# 2_-_Position2Go_Microcontroller.net
KiCad netlist of a schematic drawn in Altium Designer
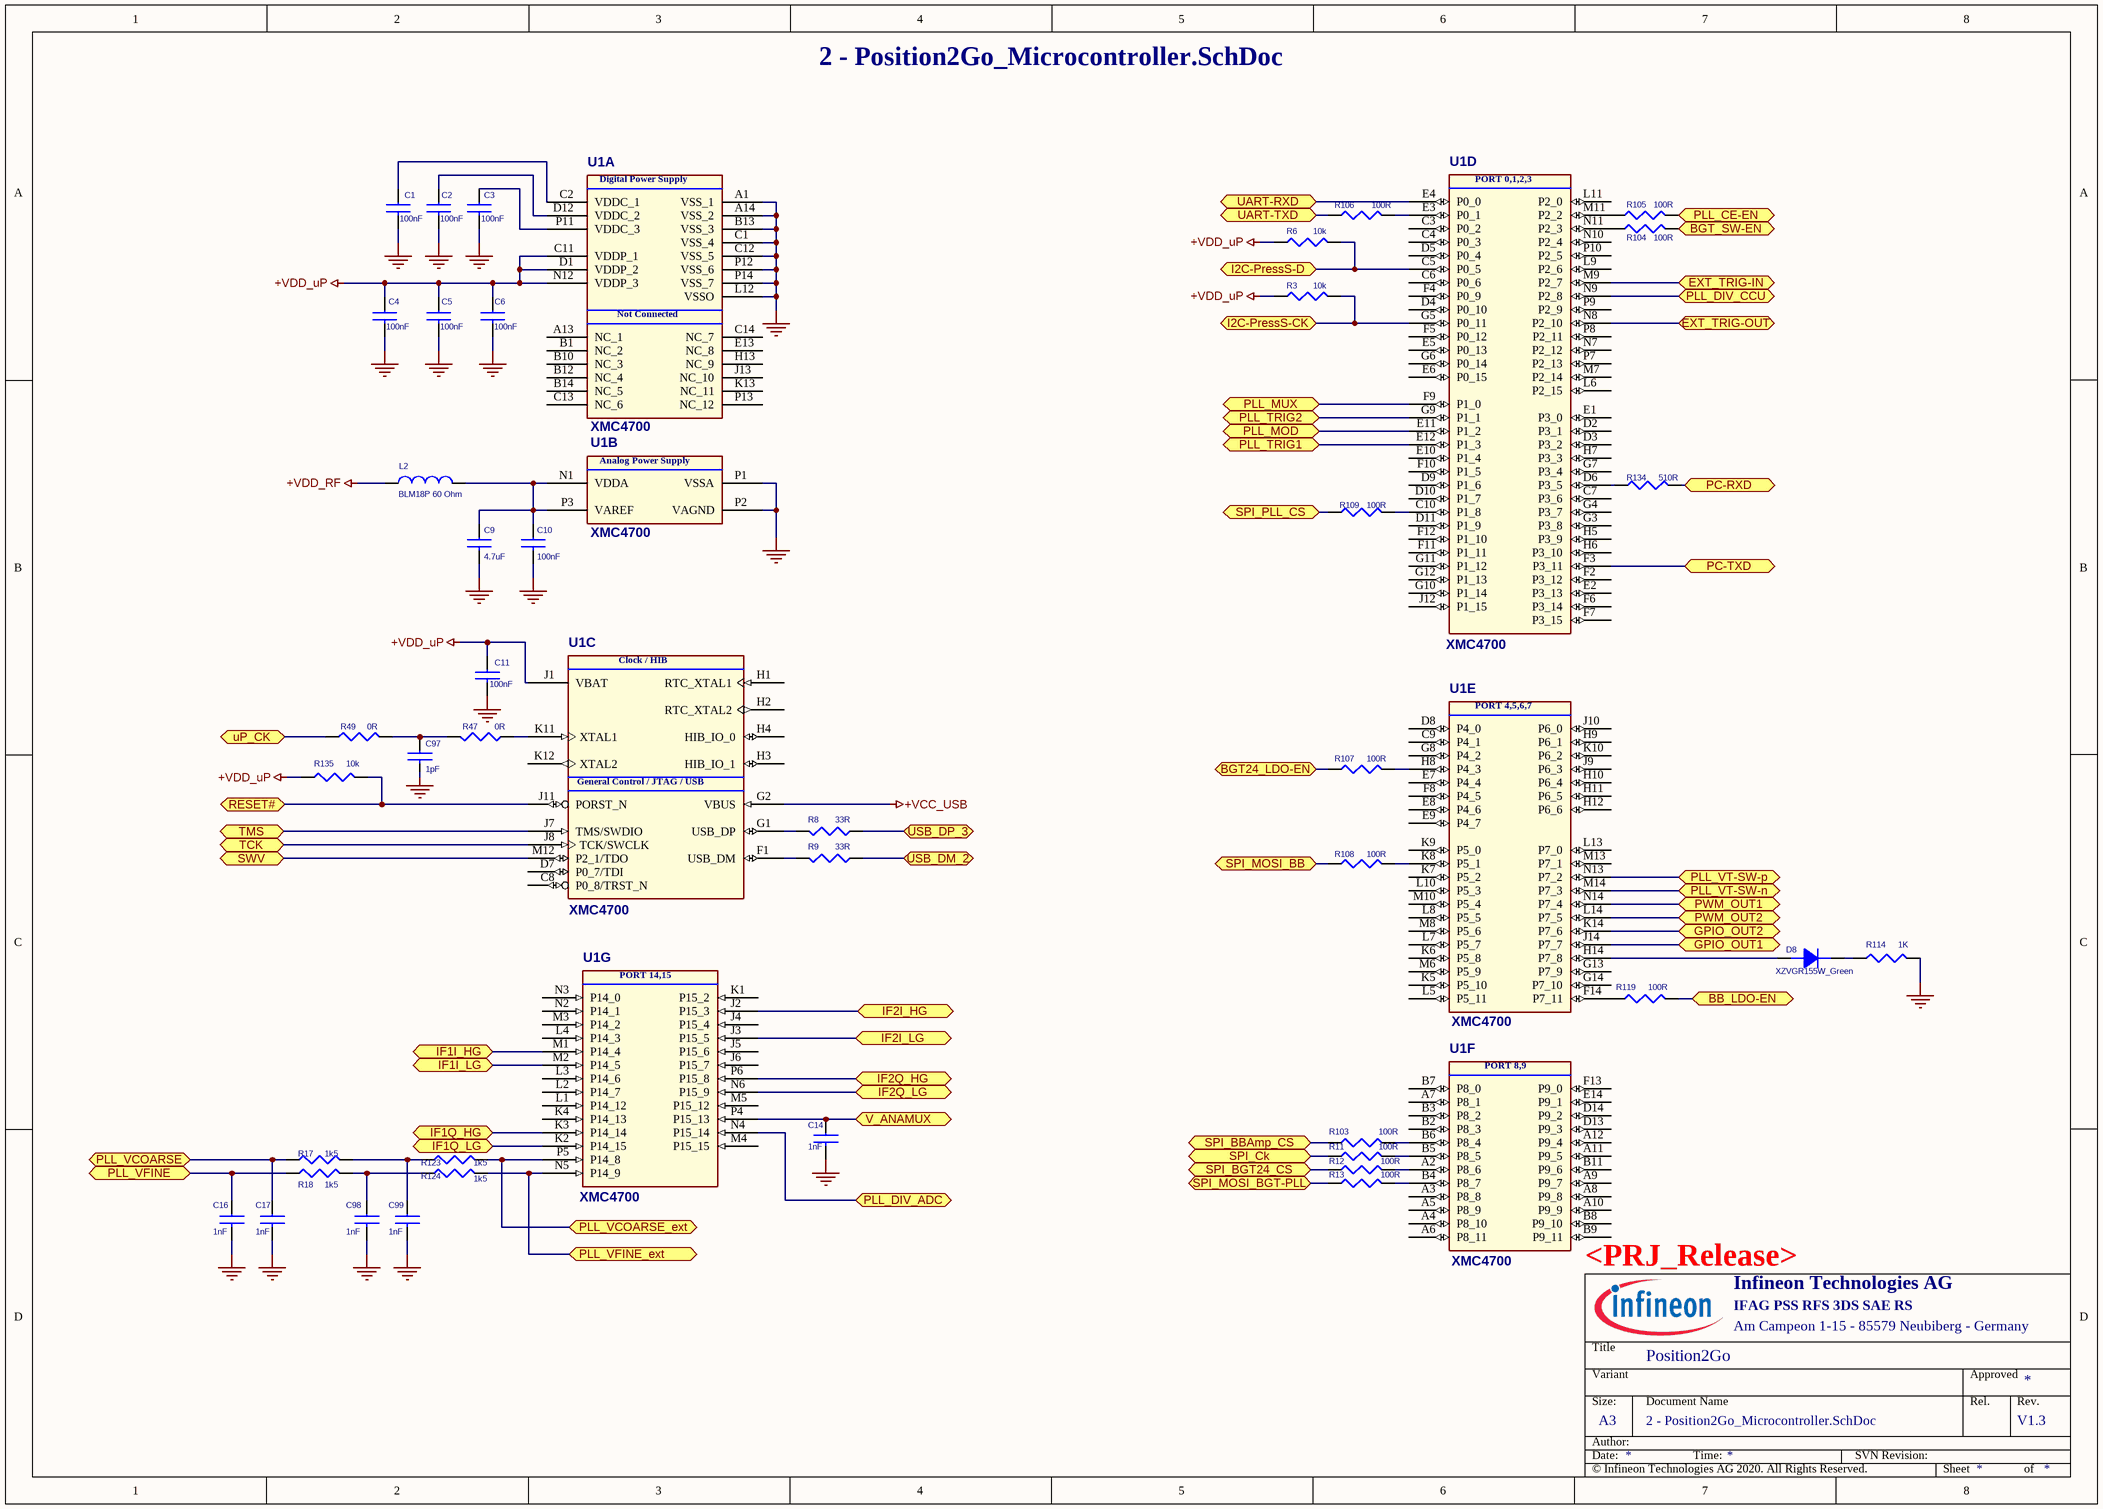
[diagram p0: 2 - Position2Go_Microcontroller.SchDoc]

(export (version "E")
  (design (tool "Eeschema 10.0.6"))
  (components
    (comp (ref "C1")
      (value "100nF")
      (footprint "C_0201")
      (description "100nF  ±10%  35V  X5R")
      (fields (field (name "VOLTAGE") "35V") (field (name "TOLERANCE") "10%"))
      (libsource (lib "*") (part "100nF_Dup1"))
    )
    (comp (ref "C2")
      (value "100nF")
      (footprint "C_0201")
      (description "100nF  ±10%  35V  X5R")
      (fields (field (name "VOLTAGE") "35V") (field (name "TOLERANCE") "10%"))
      (libsource (lib "*") (part "100nF_Dup1"))
    )
    (comp (ref "C3")
      (value "100nF")
      (footprint "C_0201")
      (description "100nF  ±10%  35V  X5R")
      (fields (field (name "VOLTAGE") "35V") (field (name "TOLERANCE") "10%"))
      (libsource (lib "*") (part "100nF_Dup1"))
    )
    (comp (ref "C4")
      (value "100nF")
      (footprint "C_0201")
      (description "100nF  ±10%  35V  X5R")
      (fields (field (name "VOLTAGE") "35V") (field (name "TOLERANCE") "10%"))
      (libsource (lib "*") (part "100nF_Dup1"))
    )
    (comp (ref "C5")
      (value "100nF")
      (footprint "C_0201")
      (description "100nF  ±10%  35V  X5R")
      (fields (field (name "VOLTAGE") "35V") (field (name "TOLERANCE") "10%"))
      (libsource (lib "*") (part "100nF_Dup1"))
    )
    (comp (ref "C6")
      (value "100nF")
      (footprint "C_0201")
      (description "100nF  ±10%  35V  X5R")
      (fields (field (name "VOLTAGE") "35V") (field (name "TOLERANCE") "10%"))
      (libsource (lib "*") (part "100nF_Dup1"))
    )
    (comp (ref "C9")
      (value "4.7uF")
      (footprint "0402_durac")
      (fields (field (name "VOLTAGE") "10V") (field (name "TOLERANCE") "10%"))
      (libsource (lib "*") (part "4.7UF"))
    )
    (comp (ref "C10")
      (value "100nF")
      (footprint "C_0201")
      (description "100nF  ±10%  35V  X5R")
      (fields (field (name "VOLTAGE") "35V") (field (name "TOLERANCE") "10%"))
      (libsource (lib "*") (part "100nF_Dup1"))
    )
    (comp (ref "C11")
      (value "100nF")
      (footprint "C_0201")
      (description "100nF  ±10%  35V  X5R")
      (fields (field (name "VOLTAGE") "35V") (field (name "TOLERANCE") "10%"))
      (libsource (lib "*") (part "100nF_Dup1"))
    )
    (comp (ref "C14")
      (value "1nF")
      (footprint "C_0201")
      (fields (field (name "TOLERANCE") "10%") (field (name "VOLTAGE") "25V"))
      (libsource (lib "*") (part "1nF"))
    )
    (comp (ref "C16")
      (value "1nF")
      (footprint "C_0201")
      (fields (field (name "TOLERANCE") "10%") (field (name "VOLTAGE") "25V"))
      (libsource (lib "*") (part "1nF"))
    )
    (comp (ref "C17")
      (value "1nF")
      (footprint "C_0201")
      (fields (field (name "TOLERANCE") "10%") (field (name "VOLTAGE") "25V"))
      (libsource (lib "*") (part "1nF"))
    )
    (comp (ref "C97")
      (value "1pF")
      (footprint "C_0201")
      (fields (field (name "TOLERANCE") "±0,1 pF") (field (name "VOLTAGE") "25V"))
      (libsource (lib "*") (part "1pF"))
    )
    (comp (ref "C98")
      (value "1nF")
      (footprint "0402_durac")
      (fields (field (name "VOLTAGE") "50V") (field (name "TOLERANCE") "5%"))
      (libsource (lib "*") (part "1.0nF"))
    )
    (comp (ref "C99")
      (value "1nF")
      (footprint "0402_durac")
      (fields (field (name "VOLTAGE") "50V") (field (name "TOLERANCE") "5%"))
      (libsource (lib "*") (part "1.0nF"))
    )
    (comp (ref "D8")
      (value "XZVGR155W_Green")
      (footprint "LED_0201")
      (libsource (lib "*") (part "LED_0201_GREEN"))
    )
    (comp (ref "L2")
      (value "BLM18P 60 Ohm")
      (footprint "L_0603")
      (libsource (lib "*") (part "blm18 p 60 ohm"))
    )
    (comp (ref "R3")
      (value "10k")
      (footprint "R_0201")
      (fields (field (name "TOLERANCE") "1%") (field (name "POWER") "0.063W"))
      (libsource (lib "*") (part "10K_Dup1"))
    )
    (comp (ref "R6")
      (value "10k")
      (footprint "R_0201")
      (fields (field (name "TOLERANCE") "1%") (field (name "POWER") "0.063W"))
      (libsource (lib "*") (part "10K_Dup1"))
    )
    (comp (ref "R8") (value "33R") (footprint "0402_durac") (libsource (lib "*") (part "RESISTOR")))
    (comp (ref "R9") (value "33R") (footprint "0402_durac") (libsource (lib "*") (part "RESISTOR")))
    (comp (ref "R11")
      (value "100R")
      (footprint "R_0201")
      (fields (field (name "TOLERANCE") "1%") (field (name "POWER") "0.063W"))
      (libsource (lib "*") (part "100"))
    )
    (comp (ref "R12")
      (value "100R")
      (footprint "R_0201")
      (fields (field (name "TOLERANCE") "1%") (field (name "POWER") "0.063W"))
      (libsource (lib "*") (part "100"))
    )
    (comp (ref "R13")
      (value "100R")
      (footprint "R_0201")
      (fields (field (name "TOLERANCE") "1%") (field (name "POWER") "0.063W"))
      (libsource (lib "*") (part "100"))
    )
    (comp (ref "R17")
      (value "1k5")
      (footprint "R_0201")
      (fields (field (name "TOLERANCE") "1%") (field (name "POWER") "0.063W"))
      (libsource (lib "*") (part "1k5"))
    )
    (comp (ref "R18")
      (value "1k5")
      (footprint "R_0201")
      (fields (field (name "TOLERANCE") "1%") (field (name "POWER") "0.063W"))
      (libsource (lib "*") (part "1k5"))
    )
    (comp (ref "R47")
      (value "0R")
      (footprint "R_0201")
      (fields (field (name "TOLERANCE") "1%") (field (name "POWER") "0.063W"))
      (libsource (lib "*") (part "0_Dup2"))
    )
    (comp (ref "R49")
      (value "0R")
      (footprint "R_0201")
      (fields (field (name "TOLERANCE") "1%") (field (name "POWER") "0.063W"))
      (libsource (lib "*") (part "0_Dup2"))
    )
    (comp (ref "R103")
      (value "100R")
      (footprint "R_0201")
      (fields (field (name "TOLERANCE") "1%") (field (name "POWER") "0.063W"))
      (libsource (lib "*") (part "100"))
    )
    (comp (ref "R104")
      (value "100R")
      (footprint "R_0201")
      (fields (field (name "TOLERANCE") "1%") (field (name "POWER") "0.063W"))
      (libsource (lib "*") (part "100"))
    )
    (comp (ref "R105")
      (value "100R")
      (footprint "R_0201")
      (fields (field (name "TOLERANCE") "1%") (field (name "POWER") "0.063W"))
      (libsource (lib "*") (part "100"))
    )
    (comp (ref "R106")
      (value "100R")
      (footprint "R_0201")
      (fields (field (name "TOLERANCE") "1%") (field (name "POWER") "0.063W"))
      (libsource (lib "*") (part "100"))
    )
    (comp (ref "R107")
      (value "100R")
      (footprint "R_0201")
      (fields (field (name "TOLERANCE") "1%") (field (name "POWER") "0.063W"))
      (libsource (lib "*") (part "100"))
    )
    (comp (ref "R108")
      (value "100R")
      (footprint "R_0201")
      (fields (field (name "TOLERANCE") "1%") (field (name "POWER") "0.063W"))
      (libsource (lib "*") (part "100"))
    )
    (comp (ref "R109")
      (value "100R")
      (footprint "R_0201")
      (fields (field (name "TOLERANCE") "1%") (field (name "POWER") "0.063W"))
      (libsource (lib "*") (part "100"))
    )
    (comp (ref "R114")
      (value "1K")
      (footprint "R_0201")
      (fields (field (name "POWER") "0.063W") (field (name "TOLERANCE") "1%"))
      (libsource (lib "*") (part "1K"))
    )
    (comp (ref "R119")
      (value "100R")
      (footprint "R_0201")
      (fields (field (name "TOLERANCE") "1%") (field (name "POWER") "0.063W"))
      (libsource (lib "*") (part "100"))
    )
    (comp (ref "R123")
      (value "1k5")
      (footprint "R_0201")
      (fields (field (name "TOLERANCE") "1%") (field (name "POWER") "0.063W"))
      (libsource (lib "*") (part "1k5"))
    )
    (comp (ref "R124")
      (value "1k5")
      (footprint "R_0201")
      (fields (field (name "TOLERANCE") "1%") (field (name "POWER") "0.063W"))
      (libsource (lib "*") (part "1k5"))
    )
    (comp (ref "R134")
      (value "510R")
      (footprint "0402_durac")
      (fields (field (name "POWER") "0.063W") (field (name "TOLERANCE") "1%"))
      (libsource (lib "*") (part "510"))
    )
    (comp (ref "R135")
      (value "10k")
      (footprint "R_0201")
      (fields (field (name "TOLERANCE") "1%") (field (name "POWER") "0.063W"))
      (libsource (lib "*") (part "10K_Dup1"))
    )
    (comp (ref "U1")
      (value "XMC4700")
      (footprint "BGA196C80P14X14_1200X1200X170")
      (libsource (lib "*") (part "XMC4700-E196F2048"))
    )
  )
  (nets
    (net (code "1") (name "+VCC_USB") (class "Default")
      (node (ref "U1") (pin "G2") (pinfunction "VBUS_G2") (pintype "input"))
    )
    (net (code "2") (name "+VDD_RF") (class "Default")
      (node (ref "L2") (pin "1") (pinfunction "1_1") (pintype "passive"))
    )
    (net (code "3") (name "+VDD_uP") (class "Default")
      (node (ref "C11") (pin "1") (pinfunction "1_1") (pintype "passive"))
      (node (ref "C4") (pin "1") (pinfunction "1_1") (pintype "passive"))
      (node (ref "C5") (pin "1") (pinfunction "1_1") (pintype "passive"))
      (node (ref "C6") (pin "1") (pinfunction "1_1") (pintype "passive"))
      (node (ref "R135") (pin "2") (pinfunction "2_2") (pintype "passive"))
      (node (ref "R3") (pin "1") (pinfunction "1_1") (pintype "passive"))
      (node (ref "R6") (pin "2") (pinfunction "2_2") (pintype "passive"))
      (node (ref "U1") (pin "C11") (pinfunction "VDDP_1_C11") (pintype "power_in"))
      (node (ref "U1") (pin "D1") (pinfunction "VDDP_2_D1") (pintype "power_in"))
      (node (ref "U1") (pin "J1") (pinfunction "VBAT_J1") (pintype "power_in"))
      (node (ref "U1") (pin "N12") (pinfunction "VDDP_3_N12") (pintype "power_in"))
    )
    (net (code "4") (name "/BB_LDO-EN") (class "Default")
      (node (ref "R119") (pin "1") (pinfunction "1_1") (pintype "passive"))
    )
    (net (code "5") (name "/BGT24_LDO-EN") (class "Default")
      (node (ref "R107") (pin "1") (pinfunction "1_1") (pintype "passive"))
    )
    (net (code "6") (name "/BGT_SW-EN") (class "Default")
      (node (ref "R104") (pin "2") (pinfunction "2_2") (pintype "passive"))
    )
    (net (code "7") (name "/EXT_TRIG-IN") (class "Default")
      (node (ref "U1") (pin "M9") (pinfunction "P2_7_M9") (pintype "bidirectional"))
    )
    (net (code "8") (name "/EXT_TRIG-OUT") (class "Default")
      (node (ref "U1") (pin "N8") (pinfunction "P2_10_N8") (pintype "bidirectional"))
    )
    (net (code "9") (name "/GPIO_OUT1") (class "Default")
      (node (ref "U1") (pin "J14") (pinfunction "P7_7_J14") (pintype "bidirectional"))
    )
    (net (code "10") (name "/GPIO_OUT2") (class "Default")
      (node (ref "U1") (pin "K14") (pinfunction "P7_6_K14") (pintype "bidirectional"))
    )
    (net (code "11") (name "/I2C-PressS-CK") (class "Default")
      (node (ref "R3") (pin "2") (pinfunction "2_2") (pintype "passive"))
      (node (ref "U1") (pin "G5") (pinfunction "P0_11_G5") (pintype "bidirectional"))
    )
    (net (code "12") (name "/I2C-PressS-D") (class "Default")
      (node (ref "R6") (pin "1") (pinfunction "1_1") (pintype "passive"))
      (node (ref "U1") (pin "C5") (pinfunction "P0_5_C5") (pintype "bidirectional"))
    )
    (net (code "13") (name "/IF1I_HG") (class "Default")
      (node (ref "U1") (pin "M1") (pinfunction "P14_4_M1") (pintype "input"))
    )
    (net (code "14") (name "/IF1I_LG") (class "Default")
      (node (ref "U1") (pin "M2") (pinfunction "P14_5_M2") (pintype "input"))
    )
    (net (code "15") (name "/IF1Q_HG") (class "Default")
      (node (ref "U1") (pin "K3") (pinfunction "P14_14_K3") (pintype "input"))
    )
    (net (code "16") (name "/IF1Q_LG") (class "Default")
      (node (ref "U1") (pin "K2") (pinfunction "P14_15_K2") (pintype "input"))
    )
    (net (code "17") (name "/IF2I_HG") (class "Default")
      (node (ref "U1") (pin "J2") (pinfunction "P15_3_J2") (pintype "input"))
    )
    (net (code "18") (name "/IF2I_LG") (class "Default")
      (node (ref "U1") (pin "J3") (pinfunction "P15_5_J3") (pintype "input"))
    )
    (net (code "19") (name "/IF2Q_HG") (class "Default")
      (node (ref "U1") (pin "P6") (pinfunction "P15_8_P6") (pintype "input"))
    )
    (net (code "20") (name "/IF2Q_LG") (class "Default")
      (node (ref "U1") (pin "N6") (pinfunction "P15_9_N6") (pintype "input"))
    )
    (net (code "21") (name "/PC-RXD") (class "Default")
      (node (ref "R134") (pin "2") (pinfunction "2_2") (pintype "passive"))
    )
    (net (code "22") (name "/PC-TXD") (class "Default")
      (node (ref "U1") (pin "F3") (pinfunction "P3_11_F3") (pintype "bidirectional"))
    )
    (net (code "23") (name "/PLL_CE-EN") (class "Default")
      (node (ref "R105") (pin "2") (pinfunction "2_2") (pintype "passive"))
    )
    (net (code "24") (name "/PLL_DIV_ADC") (class "Default")
      (node (ref "U1") (pin "N4") (pinfunction "P15_14_N4") (pintype "input"))
    )
    (net (code "25") (name "/PLL_DIV_CCU") (class "Default")
      (node (ref "U1") (pin "N9") (pinfunction "P2_8_N9") (pintype "bidirectional"))
    )
    (net (code "26") (name "/PLL_MOD") (class "Default")
      (node (ref "U1") (pin "E11") (pinfunction "P1_2_E11") (pintype "bidirectional"))
    )
    (net (code "27") (name "/PLL_MUX") (class "Default")
      (node (ref "U1") (pin "F9") (pinfunction "P1_0_F9") (pintype "bidirectional"))
    )
    (net (code "28") (name "/PLL_TRIG1") (class "Default")
      (node (ref "U1") (pin "E12") (pinfunction "P1_3_E12") (pintype "bidirectional"))
    )
    (net (code "29") (name "/PLL_TRIG2") (class "Default")
      (node (ref "U1") (pin "G9") (pinfunction "P1_1_G9") (pintype "bidirectional"))
    )
    (net (code "30") (name "/PLL_VCOARSE") (class "Default")
      (node (ref "C17") (pin "1") (pinfunction "1_1") (pintype "passive"))
      (node (ref "R17") (pin "1") (pinfunction "1_1") (pintype "passive"))
    )
    (net (code "31") (name "/PLL_VCOARSE_ext") (class "Default")
      (node (ref "R123") (pin "2") (pinfunction "2_2") (pintype "passive"))
      (node (ref "U1") (pin "P5") (pinfunction "P14_8_P5") (pintype "input"))
    )
    (net (code "32") (name "/PLL_VFINE") (class "Default")
      (node (ref "C16") (pin "1") (pinfunction "1_1") (pintype "passive"))
      (node (ref "R18") (pin "1") (pinfunction "1_1") (pintype "passive"))
    )
    (net (code "33") (name "/PLL_VFINE_ext") (class "Default")
      (node (ref "R124") (pin "2") (pinfunction "2_2") (pintype "passive"))
      (node (ref "U1") (pin "N5") (pinfunction "P14_9_N5") (pintype "input"))
    )
    (net (code "34") (name "/PLL_VT-SW-n") (class "Default")
      (node (ref "U1") (pin "M14") (pinfunction "P7_3_M14") (pintype "bidirectional"))
    )
    (net (code "35") (name "/PLL_VT-SW-p") (class "Default")
      (node (ref "U1") (pin "N13") (pinfunction "P7_2_N13") (pintype "bidirectional"))
    )
    (net (code "36") (name "/PWM_OUT1") (class "Default")
      (node (ref "U1") (pin "N14") (pinfunction "P7_4_N14") (pintype "bidirectional"))
    )
    (net (code "37") (name "/PWM_OUT2") (class "Default")
      (node (ref "U1") (pin "L14") (pinfunction "P7_5_L14") (pintype "bidirectional"))
    )
    (net (code "38") (name "/RESET#") (class "Default")
      (node (ref "R135") (pin "1") (pinfunction "1_1") (pintype "passive"))
      (node (ref "U1") (pin "J11") (pinfunction "PORST_N_J11") (pintype "bidirectional"))
    )
    (net (code "39") (name "/SPI_BBAmp_CS") (class "Default")
      (node (ref "R103") (pin "1") (pinfunction "1_1") (pintype "passive"))
    )
    (net (code "40") (name "/SPI_BGT24_CS") (class "Default")
      (node (ref "R12") (pin "1") (pinfunction "1_1") (pintype "passive"))
    )
    (net (code "41") (name "/SPI_Ck") (class "Default")
      (node (ref "R11") (pin "1") (pinfunction "1_1") (pintype "passive"))
    )
    (net (code "42") (name "/SPI_MOSI_BB") (class "Default")
      (node (ref "R108") (pin "1") (pinfunction "1_1") (pintype "passive"))
    )
    (net (code "43") (name "/SPI_MOSI_BGT-PLL") (class "Default")
      (node (ref "R13") (pin "1") (pinfunction "1_1") (pintype "passive"))
    )
    (net (code "44") (name "/SPI_PLL_CS") (class "Default")
      (node (ref "R109") (pin "2") (pinfunction "2_2") (pintype "passive"))
    )
    (net (code "45") (name "/SWV") (class "Default")
      (node (ref "U1") (pin "M12") (pinfunction "P2_1/TDO_M12") (pintype "bidirectional"))
    )
    (net (code "46") (name "/TCK") (class "Default")
      (node (ref "U1") (pin "J8") (pinfunction "TCK/SWCLK_J8") (pintype "input"))
    )
    (net (code "47") (name "/TMS") (class "Default")
      (node (ref "U1") (pin "J7") (pinfunction "TMS/SWDIO_J7") (pintype "input"))
    )
    (net (code "48") (name "/UART-RXD") (class "Default")
      (node (ref "U1") (pin "E4") (pinfunction "P0_0_E4") (pintype "bidirectional"))
    )
    (net (code "49") (name "/UART-TXD") (class "Default")
      (node (ref "R106") (pin "1") (pinfunction "1_1") (pintype "passive"))
    )
    (net (code "50") (name "/USB_DM_2") (class "Default")
      (node (ref "R9") (pin "1") (pinfunction "1_1") (pintype "passive"))
    )
    (net (code "51") (name "/USB_DP_3") (class "Default")
      (node (ref "R8") (pin "1") (pinfunction "1_1") (pintype "passive"))
    )
    (net (code "52") (name "/V_ANAMUX") (class "Default")
      (node (ref "C14") (pin "1") (pinfunction "1_1") (pintype "passive"))
      (node (ref "U1") (pin "P4") (pinfunction "P15_13_P4") (pintype "input"))
    )
    (net (code "53") (name "/uP_CK") (class "Default")
      (node (ref "R49") (pin "2") (pinfunction "2_2") (pintype "passive"))
    )
    (net (code "54") (name "GND_POWER") (class "Default")
      (node (ref "C1") (pin "2") (pinfunction "2_2") (pintype "passive"))
      (node (ref "C10") (pin "2") (pinfunction "2_2") (pintype "passive"))
      (node (ref "C11") (pin "2") (pinfunction "2_2") (pintype "passive"))
      (node (ref "C14") (pin "2") (pinfunction "2_2") (pintype "passive"))
      (node (ref "C16") (pin "2") (pinfunction "2_2") (pintype "passive"))
      (node (ref "C17") (pin "2") (pinfunction "2_2") (pintype "passive"))
      (node (ref "C2") (pin "2") (pinfunction "2_2") (pintype "passive"))
      (node (ref "C3") (pin "2") (pinfunction "2_2") (pintype "passive"))
      (node (ref "C4") (pin "2") (pinfunction "2_2") (pintype "passive"))
      (node (ref "C5") (pin "2") (pinfunction "2_2") (pintype "passive"))
      (node (ref "C6") (pin "2") (pinfunction "2_2") (pintype "passive"))
      (node (ref "C9") (pin "2") (pinfunction "2_2") (pintype "passive"))
      (node (ref "C97") (pin "2") (pinfunction "2_2") (pintype "passive"))
      (node (ref "C98") (pin "2") (pinfunction "2_2") (pintype "passive"))
      (node (ref "C99") (pin "2") (pinfunction "2_2") (pintype "passive"))
      (node (ref "R114") (pin "1") (pinfunction "1_1") (pintype "passive"))
      (node (ref "U1") (pin "A1") (pinfunction "VSS_1_A1") (pintype "power_in"))
      (node (ref "U1") (pin "A14") (pinfunction "VSS_2_A14") (pintype "power_in"))
      (node (ref "U1") (pin "B13") (pinfunction "VSS_3_B13") (pintype "power_in"))
      (node (ref "U1") (pin "C1") (pinfunction "VSS_4_C1") (pintype "power_in"))
      (node (ref "U1") (pin "C12") (pinfunction "VSS_5_C12") (pintype "power_in"))
      (node (ref "U1") (pin "L12") (pinfunction "VSSO_L12") (pintype "power_in"))
      (node (ref "U1") (pin "P1") (pinfunction "VSSA_P1") (pintype "power_in"))
      (node (ref "U1") (pin "P12") (pinfunction "VSS_6_P12") (pintype "power_in"))
      (node (ref "U1") (pin "P14") (pinfunction "VSS_7_P14") (pintype "power_in"))
      (node (ref "U1") (pin "P2") (pinfunction "VAGND_P2") (pintype "power_in"))
    )
    (net (code "55") (name "Net-(C97-Pad1)") (class "Default")
      (node (ref "C97") (pin "1") (pinfunction "1_1") (pintype "passive"))
      (node (ref "R47") (pin "2") (pinfunction "2_2") (pintype "passive"))
      (node (ref "R49") (pin "1") (pinfunction "1_1") (pintype "passive"))
    )
    (net (code "56") (name "Net-(C98-Pad1)") (class "Default")
      (node (ref "C98") (pin "1") (pinfunction "1_1") (pintype "passive"))
      (node (ref "R124") (pin "1") (pinfunction "1_1") (pintype "passive"))
      (node (ref "R18") (pin "2") (pinfunction "2_2") (pintype "passive"))
    )
    (net (code "57") (name "Net-(C99-Pad1)") (class "Default")
      (node (ref "C99") (pin "1") (pinfunction "1_1") (pintype "passive"))
      (node (ref "R123") (pin "1") (pinfunction "1_1") (pintype "passive"))
      (node (ref "R17") (pin "2") (pinfunction "2_2") (pintype "passive"))
    )
    (net (code "58") (name "Net-(D8-A)") (class "Default")
      (node (ref "D8") (pin "2") (pinfunction "A_2") (pintype "passive"))
      (node (ref "U1") (pin "H14") (pinfunction "P7_8_H14") (pintype "bidirectional"))
    )
    (net (code "59") (name "Net-(D8-K)") (class "Default")
      (node (ref "D8") (pin "1") (pinfunction "K_1") (pintype "passive"))
      (node (ref "R114") (pin "2") (pinfunction "2_2") (pintype "passive"))
    )
    (net (code "60") (name "Net-(U1A-VDDC_1)") (class "Default")
      (node (ref "C1") (pin "1") (pinfunction "1_1") (pintype "passive"))
      (node (ref "U1") (pin "C2") (pinfunction "VDDC_1_C2") (pintype "power_in"))
    )
    (net (code "61") (name "Net-(U1A-VDDC_2)") (class "Default")
      (node (ref "C2") (pin "1") (pinfunction "1_1") (pintype "passive"))
      (node (ref "U1") (pin "D12") (pinfunction "VDDC_2_D12") (pintype "power_in"))
    )
    (net (code "62") (name "Net-(U1A-VDDC_3)") (class "Default")
      (node (ref "C3") (pin "1") (pinfunction "1_1") (pintype "passive"))
      (node (ref "U1") (pin "P11") (pinfunction "VDDC_3_P11") (pintype "power_in"))
    )
    (net (code "63") (name "Net-(U1B-VAREF)") (class "Default")
      (node (ref "C10") (pin "1") (pinfunction "1_1") (pintype "passive"))
      (node (ref "C9") (pin "1") (pinfunction "1_1") (pintype "passive"))
      (node (ref "L2") (pin "2") (pinfunction "2_2") (pintype "passive"))
      (node (ref "U1") (pin "N1") (pinfunction "VDDA_N1") (pintype "power_in"))
      (node (ref "U1") (pin "P3") (pinfunction "VAREF_P3") (pintype "power_in"))
    )
    (net (code "64") (name "Net-(U1C-USB_DM)") (class "Default")
      (node (ref "R9") (pin "2") (pinfunction "2_2") (pintype "passive"))
      (node (ref "U1") (pin "F1") (pinfunction "USB_DM_F1") (pintype "bidirectional"))
    )
    (net (code "65") (name "Net-(U1C-USB_DP)") (class "Default")
      (node (ref "R8") (pin "2") (pinfunction "2_2") (pintype "passive"))
      (node (ref "U1") (pin "G1") (pinfunction "USB_DP_G1") (pintype "bidirectional"))
    )
    (net (code "66") (name "Net-(U1C-XTAL1)") (class "Default")
      (node (ref "R47") (pin "1") (pinfunction "1_1") (pintype "passive"))
      (node (ref "U1") (pin "K11") (pinfunction "XTAL1_K11") (pintype "input"))
    )
    (net (code "67") (name "Net-(U1D-P0_1)") (class "Default")
      (node (ref "R106") (pin "2") (pinfunction "2_2") (pintype "passive"))
      (node (ref "U1") (pin "E3") (pinfunction "P0_1_E3") (pintype "bidirectional"))
    )
    (net (code "68") (name "Net-(U1D-P1_8)") (class "Default")
      (node (ref "R109") (pin "1") (pinfunction "1_1") (pintype "passive"))
      (node (ref "U1") (pin "C10") (pinfunction "P1_8_C10") (pintype "bidirectional"))
    )
    (net (code "69") (name "Net-(U1D-P2_2)") (class "Default")
      (node (ref "R105") (pin "1") (pinfunction "1_1") (pintype "passive"))
      (node (ref "U1") (pin "M11") (pinfunction "P2_2_M11") (pintype "bidirectional"))
    )
    (net (code "70") (name "Net-(U1D-P2_3)") (class "Default")
      (node (ref "R104") (pin "1") (pinfunction "1_1") (pintype "passive"))
      (node (ref "U1") (pin "N11") (pinfunction "P2_3_N11") (pintype "bidirectional"))
    )
    (net (code "71") (name "Net-(U1D-P3_5)") (class "Default")
      (node (ref "R134") (pin "1") (pinfunction "1_1") (pintype "passive"))
      (node (ref "U1") (pin "D6") (pinfunction "P3_5_D6") (pintype "bidirectional"))
    )
    (net (code "72") (name "Net-(U1E-P4_3)") (class "Default")
      (node (ref "R107") (pin "2") (pinfunction "2_2") (pintype "passive"))
      (node (ref "U1") (pin "H8") (pinfunction "P4_3_H8") (pintype "bidirectional"))
    )
    (net (code "73") (name "Net-(U1E-P5_1)") (class "Default")
      (node (ref "R108") (pin "2") (pinfunction "2_2") (pintype "passive"))
      (node (ref "U1") (pin "K8") (pinfunction "P5_1_K8") (pintype "bidirectional"))
    )
    (net (code "74") (name "Net-(U1E-P7_11)") (class "Default")
      (node (ref "R119") (pin "2") (pinfunction "2_2") (pintype "passive"))
      (node (ref "U1") (pin "F14") (pinfunction "P7_11_F14") (pintype "bidirectional"))
    )
    (net (code "75") (name "Net-(U1F-P8_4)") (class "Default")
      (node (ref "R103") (pin "2") (pinfunction "2_2") (pintype "passive"))
      (node (ref "U1") (pin "B6") (pinfunction "P8_4_B6") (pintype "bidirectional"))
    )
    (net (code "76") (name "Net-(U1F-P8_5)") (class "Default")
      (node (ref "R11") (pin "2") (pinfunction "2_2") (pintype "passive"))
      (node (ref "U1") (pin "B5") (pinfunction "P8_5_B5") (pintype "bidirectional"))
    )
    (net (code "77") (name "Net-(U1F-P8_6)") (class "Default")
      (node (ref "R12") (pin "2") (pinfunction "2_2") (pintype "passive"))
      (node (ref "U1") (pin "A2") (pinfunction "P8_6_A2") (pintype "bidirectional"))
    )
    (net (code "78") (name "Net-(U1F-P8_7)") (class "Default")
      (node (ref "R13") (pin "2") (pinfunction "2_2") (pintype "passive"))
      (node (ref "U1") (pin "B4") (pinfunction "P8_7_B4") (pintype "bidirectional"))
    )
    (net (code "79") (name "unconnected-(U1A-NC_1-PadA13)") (class "Default")
      (node (ref "U1") (pin "A13") (pinfunction "NC_1_A13") (pintype "passive"))
    )
    (net (code "80") (name "unconnected-(U1A-NC_2-PadB1)") (class "Default")
      (node (ref "U1") (pin "B1") (pinfunction "NC_2_B1") (pintype "passive"))
    )
    (net (code "81") (name "unconnected-(U1A-NC_3-PadB10)") (class "Default")
      (node (ref "U1") (pin "B10") (pinfunction "NC_3_B10") (pintype "passive"))
    )
    (net (code "82") (name "unconnected-(U1A-NC_4-PadB12)") (class "Default")
      (node (ref "U1") (pin "B12") (pinfunction "NC_4_B12") (pintype "passive"))
    )
    (net (code "83") (name "unconnected-(U1A-NC_5-PadB14)") (class "Default")
      (node (ref "U1") (pin "B14") (pinfunction "NC_5_B14") (pintype "passive"))
    )
    (net (code "84") (name "unconnected-(U1A-NC_6-PadC13)") (class "Default")
      (node (ref "U1") (pin "C13") (pinfunction "NC_6_C13") (pintype "passive"))
    )
    (net (code "85") (name "unconnected-(U1A-NC_7-PadC14)") (class "Default")
      (node (ref "U1") (pin "C14") (pinfunction "NC_7_C14") (pintype "passive"))
    )
    (net (code "86") (name "unconnected-(U1A-NC_8-PadE13)") (class "Default")
      (node (ref "U1") (pin "E13") (pinfunction "NC_8_E13") (pintype "passive"))
    )
    (net (code "87") (name "unconnected-(U1A-NC_9-PadH13)") (class "Default")
      (node (ref "U1") (pin "H13") (pinfunction "NC_9_H13") (pintype "passive"))
    )
    (net (code "88") (name "unconnected-(U1A-NC_10-PadJ13)") (class "Default")
      (node (ref "U1") (pin "J13") (pinfunction "NC_10_J13") (pintype "passive"))
    )
    (net (code "89") (name "unconnected-(U1A-NC_11-PadK13)") (class "Default")
      (node (ref "U1") (pin "K13") (pinfunction "NC_11_K13") (pintype "passive"))
    )
    (net (code "90") (name "unconnected-(U1A-NC_12-PadP13)") (class "Default")
      (node (ref "U1") (pin "P13") (pinfunction "NC_12_P13") (pintype "passive"))
    )
    (net (code "91") (name "unconnected-(U1C-HIB_IO_0-PadH4)") (class "Default")
      (node (ref "U1") (pin "H4") (pinfunction "HIB_IO_0_H4") (pintype "bidirectional"))
    )
    (net (code "92") (name "unconnected-(U1C-HIB_IO_1-PadH3)") (class "Default")
      (node (ref "U1") (pin "H3") (pinfunction "HIB_IO_1_H3") (pintype "bidirectional"))
    )
    (net (code "93") (name "unconnected-(U1C-P0_7{slash}TDI-PadD7)") (class "Default")
      (node (ref "U1") (pin "D7") (pinfunction "P0_7/TDI_D7") (pintype "bidirectional"))
    )
    (net (code "94") (name "unconnected-(U1C-P0_8{slash}TRST_N-PadC8)") (class "Default")
      (node (ref "U1") (pin "C8") (pinfunction "P0_8/TRST_N_C8") (pintype "bidirectional"))
    )
    (net (code "95") (name "unconnected-(U1C-RTC_XTAL1-PadH1)") (class "Default")
      (node (ref "U1") (pin "H1") (pinfunction "RTC_XTAL1_H1") (pintype "input"))
    )
    (net (code "96") (name "unconnected-(U1C-RTC_XTAL2-PadH2)") (class "Default")
      (node (ref "U1") (pin "H2") (pinfunction "RTC_XTAL2_H2") (pintype "output"))
    )
    (net (code "97") (name "unconnected-(U1C-XTAL2-PadK12)") (class "Default")
      (node (ref "U1") (pin "K12") (pinfunction "XTAL2_K12") (pintype "output"))
    )
    (net (code "98") (name "unconnected-(U1D-P0_2-PadC3)") (class "Default")
      (node (ref "U1") (pin "C3") (pinfunction "P0_2_C3") (pintype "bidirectional"))
    )
    (net (code "99") (name "unconnected-(U1D-P0_3-PadC4)") (class "Default")
      (node (ref "U1") (pin "C4") (pinfunction "P0_3_C4") (pintype "bidirectional"))
    )
    (net (code "100") (name "unconnected-(U1D-P0_4-PadD5)") (class "Default")
      (node (ref "U1") (pin "D5") (pinfunction "P0_4_D5") (pintype "bidirectional"))
    )
    (net (code "101") (name "unconnected-(U1D-P0_6-PadC6)") (class "Default")
      (node (ref "U1") (pin "C6") (pinfunction "P0_6_C6") (pintype "bidirectional"))
    )
    (net (code "102") (name "unconnected-(U1D-P0_9-PadF4)") (class "Default")
      (node (ref "U1") (pin "F4") (pinfunction "P0_9_F4") (pintype "bidirectional"))
    )
    (net (code "103") (name "unconnected-(U1D-P0_10-PadD4)") (class "Default")
      (node (ref "U1") (pin "D4") (pinfunction "P0_10_D4") (pintype "bidirectional"))
    )
    (net (code "104") (name "unconnected-(U1D-P0_12-PadF5)") (class "Default")
      (node (ref "U1") (pin "F5") (pinfunction "P0_12_F5") (pintype "bidirectional"))
    )
    (net (code "105") (name "unconnected-(U1D-P0_13-PadE5)") (class "Default")
      (node (ref "U1") (pin "E5") (pinfunction "P0_13_E5") (pintype "bidirectional"))
    )
    (net (code "106") (name "unconnected-(U1D-P0_14-PadG6)") (class "Default")
      (node (ref "U1") (pin "G6") (pinfunction "P0_14_G6") (pintype "bidirectional"))
    )
    (net (code "107") (name "unconnected-(U1D-P0_15-PadE6)") (class "Default")
      (node (ref "U1") (pin "E6") (pinfunction "P0_15_E6") (pintype "bidirectional"))
    )
    (net (code "108") (name "unconnected-(U1D-P1_4-PadE10)") (class "Default")
      (node (ref "U1") (pin "E10") (pinfunction "P1_4_E10") (pintype "bidirectional"))
    )
    (net (code "109") (name "unconnected-(U1D-P1_5-PadF10)") (class "Default")
      (node (ref "U1") (pin "F10") (pinfunction "P1_5_F10") (pintype "bidirectional"))
    )
    (net (code "110") (name "unconnected-(U1D-P1_6-PadD9)") (class "Default")
      (node (ref "U1") (pin "D9") (pinfunction "P1_6_D9") (pintype "bidirectional"))
    )
    (net (code "111") (name "unconnected-(U1D-P1_7-PadD10)") (class "Default")
      (node (ref "U1") (pin "D10") (pinfunction "P1_7_D10") (pintype "bidirectional"))
    )
    (net (code "112") (name "unconnected-(U1D-P1_9-PadD11)") (class "Default")
      (node (ref "U1") (pin "D11") (pinfunction "P1_9_D11") (pintype "bidirectional"))
    )
    (net (code "113") (name "unconnected-(U1D-P1_10-PadF12)") (class "Default")
      (node (ref "U1") (pin "F12") (pinfunction "P1_10_F12") (pintype "bidirectional"))
    )
    (net (code "114") (name "unconnected-(U1D-P1_11-PadF11)") (class "Default")
      (node (ref "U1") (pin "F11") (pinfunction "P1_11_F11") (pintype "bidirectional"))
    )
    (net (code "115") (name "unconnected-(U1D-P1_12-PadG11)") (class "Default")
      (node (ref "U1") (pin "G11") (pinfunction "P1_12_G11") (pintype "bidirectional"))
    )
    (net (code "116") (name "unconnected-(U1D-P1_13-PadG12)") (class "Default")
      (node (ref "U1") (pin "G12") (pinfunction "P1_13_G12") (pintype "bidirectional"))
    )
    (net (code "117") (name "unconnected-(U1D-P1_14-PadG10)") (class "Default")
      (node (ref "U1") (pin "G10") (pinfunction "P1_14_G10") (pintype "bidirectional"))
    )
    (net (code "118") (name "unconnected-(U1D-P1_15-PadJ12)") (class "Default")
      (node (ref "U1") (pin "J12") (pinfunction "P1_15_J12") (pintype "bidirectional"))
    )
    (net (code "119") (name "unconnected-(U1D-P2_0-PadL11)") (class "Default")
      (node (ref "U1") (pin "L11") (pinfunction "P2_0_L11") (pintype "bidirectional"))
    )
    (net (code "120") (name "unconnected-(U1D-P2_4-PadN10)") (class "Default")
      (node (ref "U1") (pin "N10") (pinfunction "P2_4_N10") (pintype "bidirectional"))
    )
    (net (code "121") (name "unconnected-(U1D-P2_5-PadP10)") (class "Default")
      (node (ref "U1") (pin "P10") (pinfunction "P2_5_P10") (pintype "bidirectional"))
    )
    (net (code "122") (name "unconnected-(U1D-P2_6-PadL9)") (class "Default")
      (node (ref "U1") (pin "L9") (pinfunction "P2_6_L9") (pintype "bidirectional"))
    )
    (net (code "123") (name "unconnected-(U1D-P2_9-PadP9)") (class "Default")
      (node (ref "U1") (pin "P9") (pinfunction "P2_9_P9") (pintype "bidirectional"))
    )
    (net (code "124") (name "unconnected-(U1D-P2_11-PadP8)") (class "Default")
      (node (ref "U1") (pin "P8") (pinfunction "P2_11_P8") (pintype "bidirectional"))
    )
    (net (code "125") (name "unconnected-(U1D-P2_12-PadN7)") (class "Default")
      (node (ref "U1") (pin "N7") (pinfunction "P2_12_N7") (pintype "bidirectional"))
    )
    (net (code "126") (name "unconnected-(U1D-P2_13-PadP7)") (class "Default")
      (node (ref "U1") (pin "P7") (pinfunction "P2_13_P7") (pintype "bidirectional"))
    )
    (net (code "127") (name "unconnected-(U1D-P2_14-PadM7)") (class "Default")
      (node (ref "U1") (pin "M7") (pinfunction "P2_14_M7") (pintype "bidirectional"))
    )
    (net (code "128") (name "unconnected-(U1D-P2_15-PadL6)") (class "Default")
      (node (ref "U1") (pin "L6") (pinfunction "P2_15_L6") (pintype "bidirectional"))
    )
    (net (code "129") (name "unconnected-(U1D-P3_0-PadE1)") (class "Default")
      (node (ref "U1") (pin "E1") (pinfunction "P3_0_E1") (pintype "bidirectional"))
    )
    (net (code "130") (name "unconnected-(U1D-P3_1-PadD2)") (class "Default")
      (node (ref "U1") (pin "D2") (pinfunction "P3_1_D2") (pintype "bidirectional"))
    )
    (net (code "131") (name "unconnected-(U1D-P3_2-PadD3)") (class "Default")
      (node (ref "U1") (pin "D3") (pinfunction "P3_2_D3") (pintype "bidirectional"))
    )
    (net (code "132") (name "unconnected-(U1D-P3_3-PadH7)") (class "Default")
      (node (ref "U1") (pin "H7") (pinfunction "P3_3_H7") (pintype "bidirectional"))
    )
    (net (code "133") (name "unconnected-(U1D-P3_4-PadG7)") (class "Default")
      (node (ref "U1") (pin "G7") (pinfunction "P3_4_G7") (pintype "bidirectional"))
    )
    (net (code "134") (name "unconnected-(U1D-P3_6-PadC7)") (class "Default")
      (node (ref "U1") (pin "C7") (pinfunction "P3_6_C7") (pintype "bidirectional"))
    )
    (net (code "135") (name "unconnected-(U1D-P3_7-PadG4)") (class "Default")
      (node (ref "U1") (pin "G4") (pinfunction "P3_7_G4") (pintype "bidirectional"))
    )
    (net (code "136") (name "unconnected-(U1D-P3_8-PadG3)") (class "Default")
      (node (ref "U1") (pin "G3") (pinfunction "P3_8_G3") (pintype "bidirectional"))
    )
    (net (code "137") (name "unconnected-(U1D-P3_9-PadH5)") (class "Default")
      (node (ref "U1") (pin "H5") (pinfunction "P3_9_H5") (pintype "bidirectional"))
    )
    (net (code "138") (name "unconnected-(U1D-P3_10-PadH6)") (class "Default")
      (node (ref "U1") (pin "H6") (pinfunction "P3_10_H6") (pintype "bidirectional"))
    )
    (net (code "139") (name "unconnected-(U1D-P3_12-PadF2)") (class "Default")
      (node (ref "U1") (pin "F2") (pinfunction "P3_12_F2") (pintype "bidirectional"))
    )
    (net (code "140") (name "unconnected-(U1D-P3_13-PadE2)") (class "Default")
      (node (ref "U1") (pin "E2") (pinfunction "P3_13_E2") (pintype "bidirectional"))
    )
    (net (code "141") (name "unconnected-(U1D-P3_14-PadF6)") (class "Default")
      (node (ref "U1") (pin "F6") (pinfunction "P3_14_F6") (pintype "bidirectional"))
    )
    (net (code "142") (name "unconnected-(U1D-P3_15-PadF7)") (class "Default")
      (node (ref "U1") (pin "F7") (pinfunction "P3_15_F7") (pintype "bidirectional"))
    )
    (net (code "143") (name "unconnected-(U1E-P4_0-PadD8)") (class "Default")
      (node (ref "U1") (pin "D8") (pinfunction "P4_0_D8") (pintype "bidirectional"))
    )
    (net (code "144") (name "unconnected-(U1E-P4_1-PadC9)") (class "Default")
      (node (ref "U1") (pin "C9") (pinfunction "P4_1_C9") (pintype "bidirectional"))
    )
    (net (code "145") (name "unconnected-(U1E-P4_2-PadG8)") (class "Default")
      (node (ref "U1") (pin "G8") (pinfunction "P4_2_G8") (pintype "bidirectional"))
    )
    (net (code "146") (name "unconnected-(U1E-P4_4-PadE7)") (class "Default")
      (node (ref "U1") (pin "E7") (pinfunction "P4_4_E7") (pintype "bidirectional"))
    )
    (net (code "147") (name "unconnected-(U1E-P4_5-PadF8)") (class "Default")
      (node (ref "U1") (pin "F8") (pinfunction "P4_5_F8") (pintype "bidirectional"))
    )
    (net (code "148") (name "unconnected-(U1E-P4_6-PadE8)") (class "Default")
      (node (ref "U1") (pin "E8") (pinfunction "P4_6_E8") (pintype "bidirectional"))
    )
    (net (code "149") (name "unconnected-(U1E-P4_7-PadE9)") (class "Default")
      (node (ref "U1") (pin "E9") (pinfunction "P4_7_E9") (pintype "bidirectional"))
    )
    (net (code "150") (name "unconnected-(U1E-P5_0-PadK9)") (class "Default")
      (node (ref "U1") (pin "K9") (pinfunction "P5_0_K9") (pintype "bidirectional"))
    )
    (net (code "151") (name "unconnected-(U1E-P5_2-PadK7)") (class "Default")
      (node (ref "U1") (pin "K7") (pinfunction "P5_2_K7") (pintype "bidirectional"))
    )
    (net (code "152") (name "unconnected-(U1E-P5_3-PadL10)") (class "Default")
      (node (ref "U1") (pin "L10") (pinfunction "P5_3_L10") (pintype "bidirectional"))
    )
    (net (code "153") (name "unconnected-(U1E-P5_4-PadM10)") (class "Default")
      (node (ref "U1") (pin "M10") (pinfunction "P5_4_M10") (pintype "bidirectional"))
    )
    (net (code "154") (name "unconnected-(U1E-P5_5-PadL8)") (class "Default")
      (node (ref "U1") (pin "L8") (pinfunction "P5_5_L8") (pintype "bidirectional"))
    )
    (net (code "155") (name "unconnected-(U1E-P5_6-PadM8)") (class "Default")
      (node (ref "U1") (pin "M8") (pinfunction "P5_6_M8") (pintype "bidirectional"))
    )
    (net (code "156") (name "unconnected-(U1E-P5_7-PadL7)") (class "Default")
      (node (ref "U1") (pin "L7") (pinfunction "P5_7_L7") (pintype "bidirectional"))
    )
    (net (code "157") (name "unconnected-(U1E-P5_8-PadK6)") (class "Default")
      (node (ref "U1") (pin "K6") (pinfunction "P5_8_K6") (pintype "bidirectional"))
    )
    (net (code "158") (name "unconnected-(U1E-P5_9-PadM6)") (class "Default")
      (node (ref "U1") (pin "M6") (pinfunction "P5_9_M6") (pintype "bidirectional"))
    )
    (net (code "159") (name "unconnected-(U1E-P5_10-PadK5)") (class "Default")
      (node (ref "U1") (pin "K5") (pinfunction "P5_10_K5") (pintype "bidirectional"))
    )
    (net (code "160") (name "unconnected-(U1E-P5_11-PadL5)") (class "Default")
      (node (ref "U1") (pin "L5") (pinfunction "P5_11_L5") (pintype "bidirectional"))
    )
    (net (code "161") (name "unconnected-(U1E-P6_0-PadJ10)") (class "Default")
      (node (ref "U1") (pin "J10") (pinfunction "P6_0_J10") (pintype "bidirectional"))
    )
    (net (code "162") (name "unconnected-(U1E-P6_1-PadH9)") (class "Default")
      (node (ref "U1") (pin "H9") (pinfunction "P6_1_H9") (pintype "bidirectional"))
    )
    (net (code "163") (name "unconnected-(U1E-P6_2-PadK10)") (class "Default")
      (node (ref "U1") (pin "K10") (pinfunction "P6_2_K10") (pintype "bidirectional"))
    )
    (net (code "164") (name "unconnected-(U1E-P6_3-PadJ9)") (class "Default")
      (node (ref "U1") (pin "J9") (pinfunction "P6_3_J9") (pintype "bidirectional"))
    )
    (net (code "165") (name "unconnected-(U1E-P6_4-PadH10)") (class "Default")
      (node (ref "U1") (pin "H10") (pinfunction "P6_4_H10") (pintype "bidirectional"))
    )
    (net (code "166") (name "unconnected-(U1E-P6_5-PadH11)") (class "Default")
      (node (ref "U1") (pin "H11") (pinfunction "P6_5_H11") (pintype "bidirectional"))
    )
    (net (code "167") (name "unconnected-(U1E-P6_6-PadH12)") (class "Default")
      (node (ref "U1") (pin "H12") (pinfunction "P6_6_H12") (pintype "bidirectional"))
    )
    (net (code "168") (name "unconnected-(U1E-P7_0-PadL13)") (class "Default")
      (node (ref "U1") (pin "L13") (pinfunction "P7_0_L13") (pintype "bidirectional"))
    )
    (net (code "169") (name "unconnected-(U1E-P7_1-PadM13)") (class "Default")
      (node (ref "U1") (pin "M13") (pinfunction "P7_1_M13") (pintype "bidirectional"))
    )
    (net (code "170") (name "unconnected-(U1E-P7_9-PadG13)") (class "Default")
      (node (ref "U1") (pin "G13") (pinfunction "P7_9_G13") (pintype "bidirectional"))
    )
    (net (code "171") (name "unconnected-(U1E-P7_10-PadG14)") (class "Default")
      (node (ref "U1") (pin "G14") (pinfunction "P7_10_G14") (pintype "bidirectional"))
    )
    (net (code "172") (name "unconnected-(U1F-P8_0-PadB7)") (class "Default")
      (node (ref "U1") (pin "B7") (pinfunction "P8_0_B7") (pintype "bidirectional"))
    )
    (net (code "173") (name "unconnected-(U1F-P8_1-PadA7)") (class "Default")
      (node (ref "U1") (pin "A7") (pinfunction "P8_1_A7") (pintype "bidirectional"))
    )
    (net (code "174") (name "unconnected-(U1F-P8_2-PadB3)") (class "Default")
      (node (ref "U1") (pin "B3") (pinfunction "P8_2_B3") (pintype "bidirectional"))
    )
    (net (code "175") (name "unconnected-(U1F-P8_3-PadB2)") (class "Default")
      (node (ref "U1") (pin "B2") (pinfunction "P8_3_B2") (pintype "bidirectional"))
    )
    (net (code "176") (name "unconnected-(U1F-P8_8-PadA3)") (class "Default")
      (node (ref "U1") (pin "A3") (pinfunction "P8_8_A3") (pintype "bidirectional"))
    )
    (net (code "177") (name "unconnected-(U1F-P8_9-PadA5)") (class "Default")
      (node (ref "U1") (pin "A5") (pinfunction "P8_9_A5") (pintype "bidirectional"))
    )
    (net (code "178") (name "unconnected-(U1F-P8_10-PadA4)") (class "Default")
      (node (ref "U1") (pin "A4") (pinfunction "P8_10_A4") (pintype "bidirectional"))
    )
    (net (code "179") (name "unconnected-(U1F-P8_11-PadA6)") (class "Default")
      (node (ref "U1") (pin "A6") (pinfunction "P8_11_A6") (pintype "bidirectional"))
    )
    (net (code "180") (name "unconnected-(U1F-P9_0-PadF13)") (class "Default")
      (node (ref "U1") (pin "F13") (pinfunction "P9_0_F13") (pintype "bidirectional"))
    )
    (net (code "181") (name "unconnected-(U1F-P9_1-PadE14)") (class "Default")
      (node (ref "U1") (pin "E14") (pinfunction "P9_1_E14") (pintype "bidirectional"))
    )
    (net (code "182") (name "unconnected-(U1F-P9_2-PadD14)") (class "Default")
      (node (ref "U1") (pin "D14") (pinfunction "P9_2_D14") (pintype "bidirectional"))
    )
    (net (code "183") (name "unconnected-(U1F-P9_3-PadD13)") (class "Default")
      (node (ref "U1") (pin "D13") (pinfunction "P9_3_D13") (pintype "bidirectional"))
    )
    (net (code "184") (name "unconnected-(U1F-P9_4-PadA12)") (class "Default")
      (node (ref "U1") (pin "A12") (pinfunction "P9_4_A12") (pintype "bidirectional"))
    )
    (net (code "185") (name "unconnected-(U1F-P9_5-PadA11)") (class "Default")
      (node (ref "U1") (pin "A11") (pinfunction "P9_5_A11") (pintype "bidirectional"))
    )
    (net (code "186") (name "unconnected-(U1F-P9_6-PadB11)") (class "Default")
      (node (ref "U1") (pin "B11") (pinfunction "P9_6_B11") (pintype "bidirectional"))
    )
    (net (code "187") (name "unconnected-(U1F-P9_7-PadA9)") (class "Default")
      (node (ref "U1") (pin "A9") (pinfunction "P9_7_A9") (pintype "bidirectional"))
    )
    (net (code "188") (name "unconnected-(U1F-P9_8-PadA8)") (class "Default")
      (node (ref "U1") (pin "A8") (pinfunction "P9_8_A8") (pintype "bidirectional"))
    )
    (net (code "189") (name "unconnected-(U1F-P9_9-PadA10)") (class "Default")
      (node (ref "U1") (pin "A10") (pinfunction "P9_9_A10") (pintype "bidirectional"))
    )
    (net (code "190") (name "unconnected-(U1F-P9_10-PadB8)") (class "Default")
      (node (ref "U1") (pin "B8") (pinfunction "P9_10_B8") (pintype "bidirectional"))
    )
    (net (code "191") (name "unconnected-(U1F-P9_11-PadB9)") (class "Default")
      (node (ref "U1") (pin "B9") (pinfunction "P9_11_B9") (pintype "bidirectional"))
    )
    (net (code "192") (name "unconnected-(U1G-P14_0-PadN3)") (class "Default")
      (node (ref "U1") (pin "N3") (pinfunction "P14_0_N3") (pintype "input"))
    )
    (net (code "193") (name "unconnected-(U1G-P14_1-PadN2)") (class "Default")
      (node (ref "U1") (pin "N2") (pinfunction "P14_1_N2") (pintype "input"))
    )
    (net (code "194") (name "unconnected-(U1G-P14_2-PadM3)") (class "Default")
      (node (ref "U1") (pin "M3") (pinfunction "P14_2_M3") (pintype "input"))
    )
    (net (code "195") (name "unconnected-(U1G-P14_3-PadL4)") (class "Default")
      (node (ref "U1") (pin "L4") (pinfunction "P14_3_L4") (pintype "input"))
    )
    (net (code "196") (name "unconnected-(U1G-P14_6-PadL3)") (class "Default")
      (node (ref "U1") (pin "L3") (pinfunction "P14_6_L3") (pintype "input"))
    )
    (net (code "197") (name "unconnected-(U1G-P14_7-PadL2)") (class "Default")
      (node (ref "U1") (pin "L2") (pinfunction "P14_7_L2") (pintype "input"))
    )
    (net (code "198") (name "unconnected-(U1G-P14_12-PadL1)") (class "Default")
      (node (ref "U1") (pin "L1") (pinfunction "P14_12_L1") (pintype "input"))
    )
    (net (code "199") (name "unconnected-(U1G-P14_13-PadK4)") (class "Default")
      (node (ref "U1") (pin "K4") (pinfunction "P14_13_K4") (pintype "input"))
    )
    (net (code "200") (name "unconnected-(U1G-P15_2-PadK1)") (class "Default")
      (node (ref "U1") (pin "K1") (pinfunction "P15_2_K1") (pintype "input"))
    )
    (net (code "201") (name "unconnected-(U1G-P15_4-PadJ4)") (class "Default")
      (node (ref "U1") (pin "J4") (pinfunction "P15_4_J4") (pintype "input"))
    )
    (net (code "202") (name "unconnected-(U1G-P15_6-PadJ5)") (class "Default")
      (node (ref "U1") (pin "J5") (pinfunction "P15_6_J5") (pintype "input"))
    )
    (net (code "203") (name "unconnected-(U1G-P15_7-PadJ6)") (class "Default")
      (node (ref "U1") (pin "J6") (pinfunction "P15_7_J6") (pintype "input"))
    )
    (net (code "204") (name "unconnected-(U1G-P15_12-PadM5)") (class "Default")
      (node (ref "U1") (pin "M5") (pinfunction "P15_12_M5") (pintype "input"))
    )
    (net (code "205") (name "unconnected-(U1G-P15_15-PadM4)") (class "Default")
      (node (ref "U1") (pin "M4") (pinfunction "P15_15_M4") (pintype "input"))
    )
  )
)
